# VentaConnected_Arduino_V0_01_2017-11-22.net
KiCad netlist of a schematic drawn in EAGLE
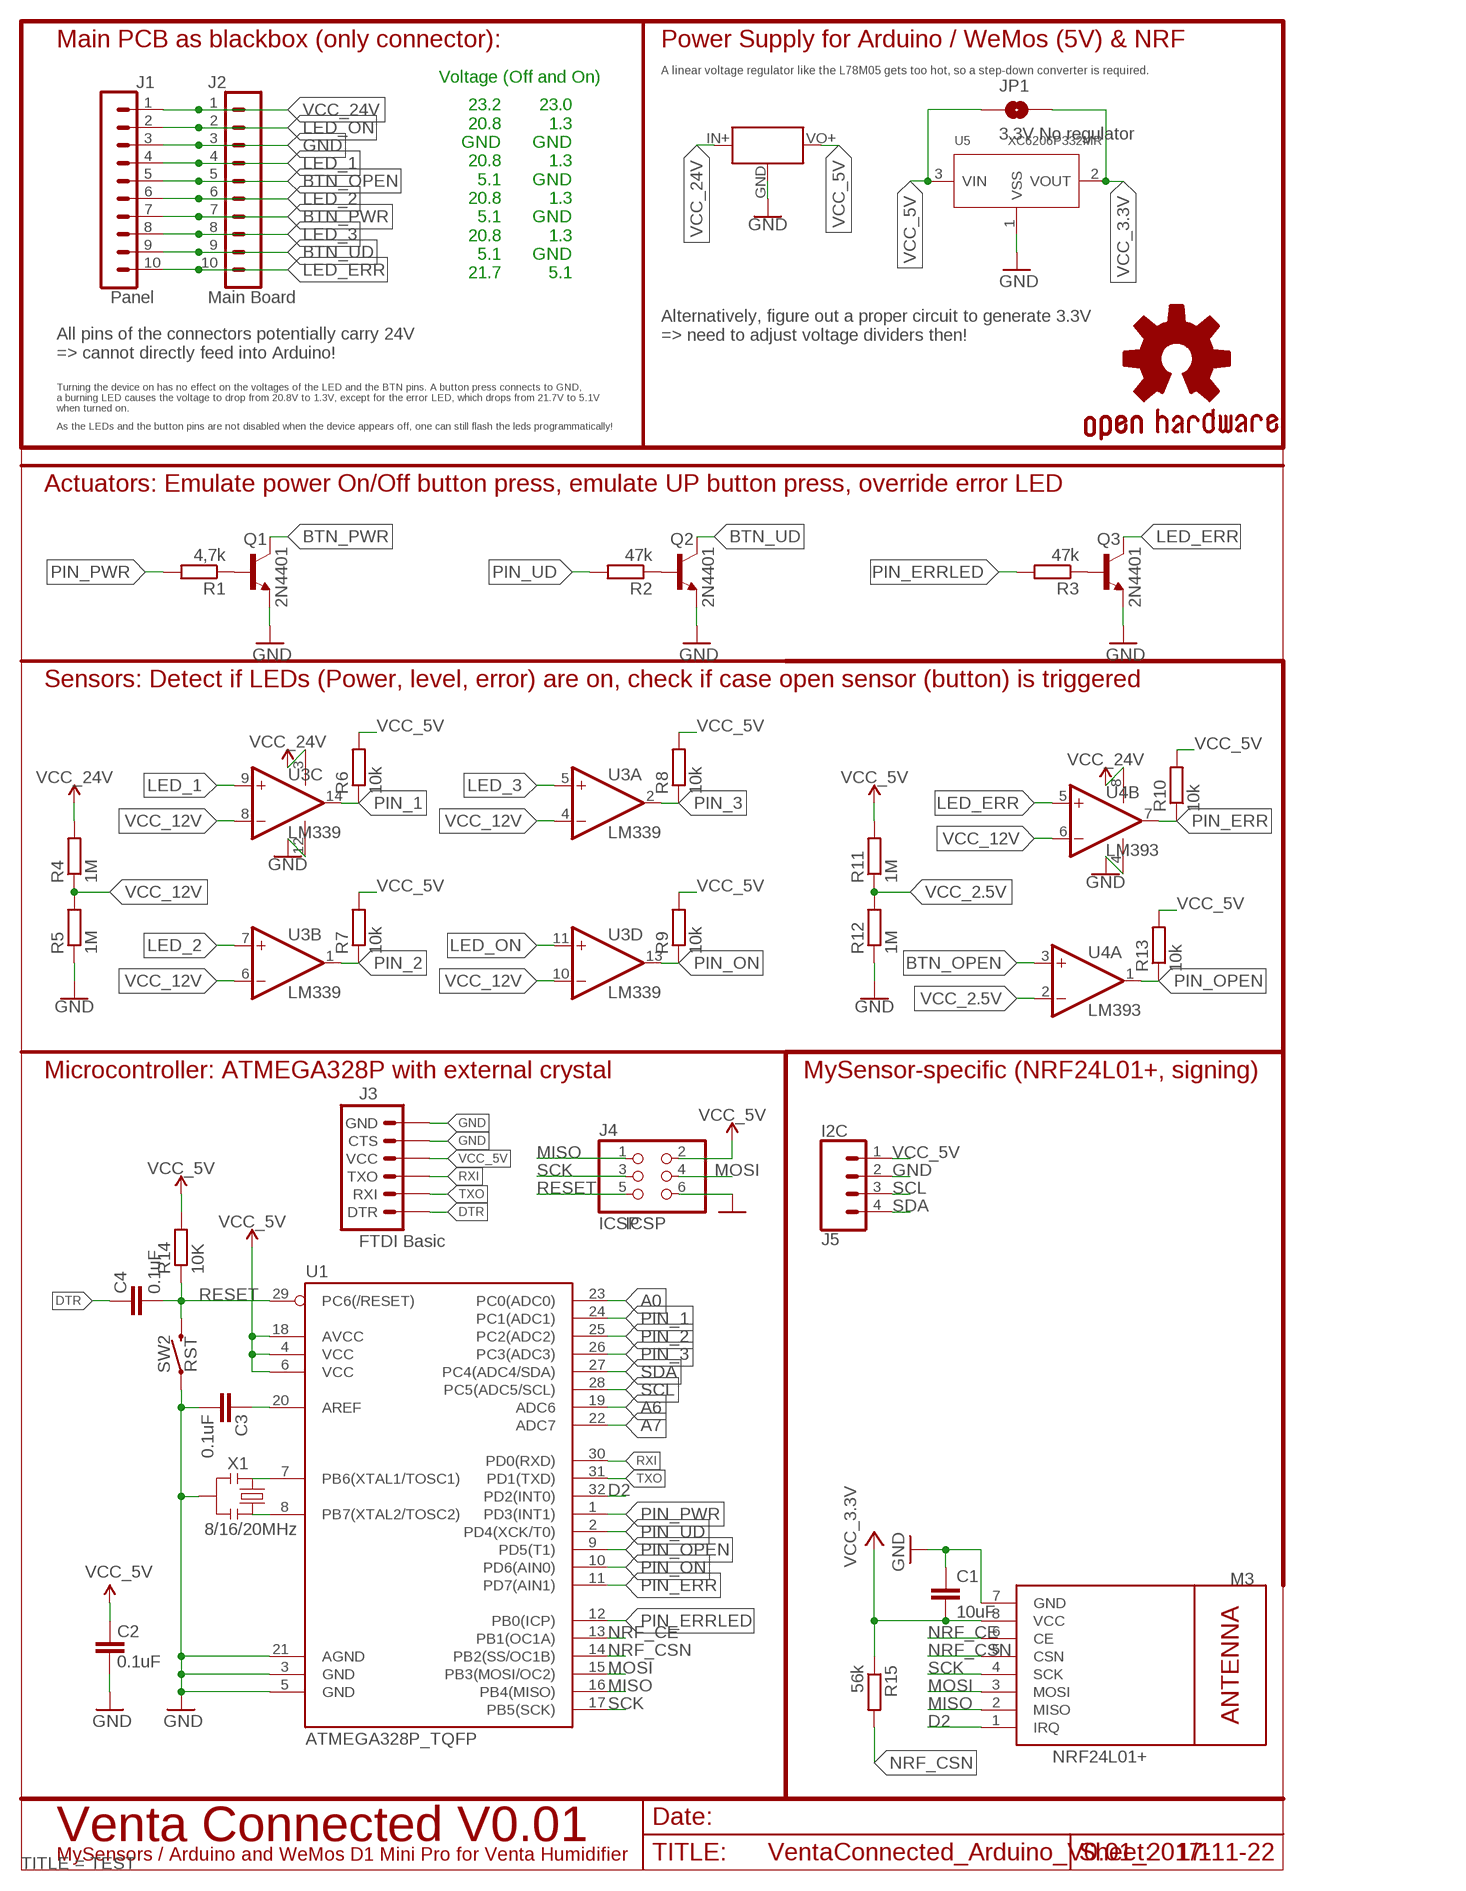
[diagram p0: schematic, sheet 1]

(export (version "E")
  (design (tool "Eeschema 10.0.6"))
  (components
    (comp (ref "C1")
      (value "10uF")
      (footprint "eagle-import:C0805")
      (libsource (lib "eagle-import") (part "C-EUC0805"))
    )
    (comp (ref "C2")
      (value "0.1uF")
      (footprint "eagle-import:0805")
      (libsource (lib "eagle-import") (part "CAP0805"))
    )
    (comp (ref "C3")
      (value "0.1uF")
      (footprint "eagle-import:0805")
      (libsource (lib "eagle-import") (part "CAP0805"))
    )
    (comp (ref "C4")
      (value "0.1uF")
      (footprint "eagle-import:0805")
      (libsource (lib "eagle-import") (part "CAP0805"))
    )
    (comp (ref "GOLD_ORB_SM1")
      (value "OSHWLOGO_GOLD_ORB_SM")
      (footprint "eagle-import:OSHW2")
      (libsource (lib "eagle-import") (part "OSHWLOGO_GOLD_ORB_SM"))
    )
    (comp (ref "J1")
      (value "Panel")
      (footprint "eagle-import:2X5-SHROUDED")
      (libsource (lib "eagle-import") (part "CONN_05X2SHD"))
    )
    (comp (ref "J2")
      (value "Main Board")
      (footprint "eagle-import:2X5")
      (libsource (lib "eagle-import") (part "CONN_05X2PTH"))
    )
    (comp (ref "J3")
      (value "FTDI Basic")
      (footprint "eagle-import:1X06")
      (libsource (lib "eagle-import") (part "ARDUINO_SERIAL_PROGRAMPTH"))
    )
    (comp (ref "J4")
      (value "ICSP")
      (footprint "eagle-import:2X03")
      (libsource (lib "eagle-import") (part "PINHD-2X3"))
    )
    (comp (ref "J5")
      (value "I2C")
      (footprint "eagle-import:1X04")
      (libsource (lib "eagle-import") (part "CONN_04"))
    )
    (comp (ref "JP1")
      (value "3.3V No regulator")
      (footprint "eagle-import:SMT-JUMPER_2_NO_SILK")
      (libsource (lib "eagle-import") (part "JUMPER-SMT_2_NO_SILK"))
    )
    (comp (ref "M3")
      (value "NRF24L01+")
      (footprint "eagle-import:WIRELESS-NRF24L01-SMD")
      (libsource (lib "eagle-import") (part "WIRELESS-NRF24L01SMD"))
    )
    (comp (ref "Q1")
      (value "2N4401")
      (footprint "eagle-import:SOT23-BEC")
      (libsource (lib "eagle-import") (part "-NPN-SOT23-BECMMBT4401LT1"))
    )
    (comp (ref "Q2")
      (value "2N4401")
      (footprint "eagle-import:SOT23-BEC")
      (libsource (lib "eagle-import") (part "-NPN-SOT23-BECMMBT4401LT1"))
    )
    (comp (ref "Q3")
      (value "2N4401")
      (footprint "eagle-import:SOT23-BEC")
      (libsource (lib "eagle-import") (part "-NPN-SOT23-BECMMBT4401LT1"))
    )
    (comp (ref "R1")
      (value "4,7k")
      (footprint "eagle-import:R0805")
      (libsource (lib "eagle-import") (part "resistor_348_R-EU_R0805"))
    )
    (comp (ref "R2")
      (value "47k")
      (footprint "eagle-import:R0805")
      (libsource (lib "eagle-import") (part "resistor_348_R-EU_R0805"))
    )
    (comp (ref "R3")
      (value "47k")
      (footprint "eagle-import:R0805")
      (libsource (lib "eagle-import") (part "resistor_348_R-EU_R0805"))
    )
    (comp (ref "R4")
      (value "1M")
      (footprint "eagle-import:R0805")
      (libsource (lib "eagle-import") (part "resistor_348_R-EU_R0805"))
    )
    (comp (ref "R5")
      (value "1M")
      (footprint "eagle-import:R0805")
      (libsource (lib "eagle-import") (part "resistor_348_R-EU_R0805"))
    )
    (comp (ref "R6")
      (value "10k")
      (footprint "eagle-import:R0805")
      (libsource (lib "eagle-import") (part "rcl_334_R-EU_R0805"))
    )
    (comp (ref "R7")
      (value "10k")
      (footprint "eagle-import:R0805")
      (libsource (lib "eagle-import") (part "rcl_334_R-EU_R0805"))
    )
    (comp (ref "R8")
      (value "10k")
      (footprint "eagle-import:R0805")
      (libsource (lib "eagle-import") (part "rcl_334_R-EU_R0805"))
    )
    (comp (ref "R9")
      (value "10k")
      (footprint "eagle-import:R0805")
      (libsource (lib "eagle-import") (part "rcl_334_R-EU_R0805"))
    )
    (comp (ref "R10")
      (value "10k")
      (footprint "eagle-import:R0805")
      (libsource (lib "eagle-import") (part "rcl_334_R-EU_R0805"))
    )
    (comp (ref "R11")
      (value "1M")
      (footprint "eagle-import:R0805")
      (libsource (lib "eagle-import") (part "resistor_348_R-EU_R0805"))
    )
    (comp (ref "R12")
      (value "1M")
      (footprint "eagle-import:R0805")
      (libsource (lib "eagle-import") (part "resistor_348_R-EU_R0805"))
    )
    (comp (ref "R13")
      (value "10k")
      (footprint "eagle-import:R0805")
      (libsource (lib "eagle-import") (part "rcl_334_R-EU_R0805"))
    )
    (comp (ref "R14")
      (value "10K")
      (footprint "eagle-import:R0805")
      (libsource (lib "eagle-import") (part "rcl_334_R-EU_R0805"))
    )
    (comp (ref "R15")
      (value "56k")
      (footprint "eagle-import:R0805")
      (libsource (lib "eagle-import") (part "R-EU_R0805"))
    )
    (comp (ref "SW2")
      (value "RST")
      (footprint "eagle-import:TACTILE_SWITCH_SMD_6.0X3.5MM")
      (libsource (lib "eagle-import") (part "MOMENTARY-SWITCH-SPST-SMD-6.0X3.5MM"))
    )
    (comp (ref "U1")
      (value "ATMEGA328P_TQFP")
      (footprint "eagle-import:TQFP32-08")
      (libsource (lib "eagle-import") (part "ATMEGA328P_TQFP"))
    )
    (comp (ref "U2")
      (value "MINI_BUCK_CONVERTER_UPSIDEDOWN")
      (footprint "eagle-import:MINI_BUCK_CONVERTER_UPDOWN")
      (libsource (lib "eagle-import") (part "MINI_BUCK_CONVERTER_UPSIDEDOWN"))
    )
    (comp (ref "U3")
      (value "LM339")
      (footprint "eagle-import:SO14")
      (libsource (lib "eagle-import") (part "TLC339D"))
    )
    (comp (ref "U4")
      (value "LM393")
      (footprint "eagle-import:SO08")
      (libsource (lib "eagle-import") (part "LM393D"))
    )
    (comp (ref "U5")
      (value "XC6206P332MR")
      (footprint "eagle-import:SOT-23")
      (fields (field (name "MPN") "XC6206P332MR-G"))
      (libsource (lib "eagle-import") (part "PMIC-LDO-XC6206P332MR-G(SOT23)"))
    )
    (comp (ref "X1")
      (value "8/16/20MHz")
      (footprint "eagle-import:RESONATOR-SMD-1_1")
      (libsource (lib "eagle-import") (part "RESONATOR1{colon}1"))
    )
  )
  (nets
    (net (code "1") (name "/D2") (class "Default")
      (node (ref "M3") (pin "1") (pinfunction "IRQ_1") (pintype "bidirectional"))
      (node (ref "U1") (pin "32") (pinfunction "PD2(INT0)_32") (pintype "bidirectional"))
    )
    (net (code "2") (name "/MISO") (class "Default")
      (node (ref "J4") (pin "1") (pinfunction "1_1") (pintype "passive"))
      (node (ref "M3") (pin "2") (pinfunction "MISO_2") (pintype "bidirectional"))
      (node (ref "U1") (pin "16") (pinfunction "PB4(MISO)_16") (pintype "bidirectional"))
    )
    (net (code "3") (name "/MOSI") (class "Default")
      (node (ref "J4") (pin "4") (pinfunction "4_4") (pintype "passive"))
      (node (ref "M3") (pin "3") (pinfunction "MOSI_3") (pintype "bidirectional"))
      (node (ref "U1") (pin "15") (pinfunction "PB3(MOSI/OC2)_15") (pintype "bidirectional"))
    )
    (net (code "4") (name "/NRF_CE") (class "Default")
      (node (ref "M3") (pin "6") (pinfunction "CE_6") (pintype "bidirectional"))
      (node (ref "U1") (pin "13") (pinfunction "PB1(OC1A)_13") (pintype "bidirectional"))
    )
    (net (code "5") (name "/RESET") (class "Default")
      (node (ref "C4") (pin "1") (pinfunction "1_1") (pintype "passive"))
      (node (ref "J4") (pin "5") (pinfunction "5_5") (pintype "passive"))
      (node (ref "R14") (pin "1") (pinfunction "1_1") (pintype "passive"))
      (node (ref "SW2") (pin "2") (pinfunction "2_2") (pintype "passive"))
      (node (ref "U1") (pin "29") (pinfunction "PC6(/RESET)_29") (pintype "bidirectional"))
    )
    (net (code "6") (name "/SCK") (class "Default")
      (node (ref "J4") (pin "3") (pinfunction "3_3") (pintype "passive"))
      (node (ref "M3") (pin "4") (pinfunction "SCK_4") (pintype "bidirectional"))
      (node (ref "U1") (pin "17") (pinfunction "PB5(SCK)_17") (pintype "bidirectional"))
    )
    (net (code "7") (name "A0") (class "Default")
      (node (ref "U1") (pin "23") (pinfunction "PC0(ADC0)_23") (pintype "bidirectional"))
    )
    (net (code "8") (name "A6") (class "Default")
      (node (ref "U1") (pin "19") (pinfunction "ADC6_19") (pintype "bidirectional"))
    )
    (net (code "9") (name "A7") (class "Default")
      (node (ref "U1") (pin "22") (pinfunction "ADC7_22") (pintype "bidirectional"))
    )
    (net (code "10") (name "BTN_OPEN") (class "Default")
      (node (ref "J1") (pin "5") (pinfunction "5_5") (pintype "passive"))
      (node (ref "J2") (pin "5") (pinfunction "5_5") (pintype "passive"))
      (node (ref "U4") (pin "3") (pinfunction "+IN_3") (pintype "input"))
    )
    (net (code "11") (name "BTN_PWR") (class "Default")
      (node (ref "J1") (pin "7") (pinfunction "7_7") (pintype "passive"))
      (node (ref "J2") (pin "7") (pinfunction "7_7") (pintype "passive"))
      (node (ref "Q1") (pin "C") (pinfunction "C_C") (pintype "passive"))
    )
    (net (code "12") (name "BTN_UD") (class "Default")
      (node (ref "J1") (pin "9") (pinfunction "9_9") (pintype "passive"))
      (node (ref "J2") (pin "9") (pinfunction "9_9") (pintype "passive"))
      (node (ref "Q2") (pin "C") (pinfunction "C_C") (pintype "passive"))
    )
    (net (code "13") (name "DTR") (class "Default")
      (node (ref "C4") (pin "2") (pinfunction "2_2") (pintype "passive"))
      (node (ref "J3") (pin "1") (pinfunction "DTR_1") (pintype "passive"))
    )
    (net (code "14") (name "GND") (class "Default")
      (node (ref "C1") (pin "1") (pinfunction "1_1") (pintype "passive"))
      (node (ref "C2") (pin "1") (pinfunction "1_1") (pintype "passive"))
      (node (ref "C3") (pin "1") (pinfunction "1_1") (pintype "passive"))
      (node (ref "J1") (pin "3") (pinfunction "3_3") (pintype "passive"))
      (node (ref "J2") (pin "3") (pinfunction "3_3") (pintype "passive"))
      (node (ref "J3") (pin "5") (pinfunction "CTS_5") (pintype "passive"))
      (node (ref "J3") (pin "6") (pinfunction "GND_6") (pintype "passive"))
      (node (ref "J4") (pin "6") (pinfunction "6_6") (pintype "passive"))
      (node (ref "J5") (pin "2") (pinfunction "2_2") (pintype "passive"))
      (node (ref "M3") (pin "7") (pinfunction "GND_7") (pintype "power_in"))
      (node (ref "Q1") (pin "E") (pinfunction "E_E") (pintype "passive"))
      (node (ref "Q2") (pin "E") (pinfunction "E_E") (pintype "passive"))
      (node (ref "Q3") (pin "E") (pinfunction "E_E") (pintype "passive"))
      (node (ref "R12") (pin "1") (pinfunction "1_1") (pintype "passive"))
      (node (ref "R5") (pin "1") (pinfunction "1_1") (pintype "passive"))
      (node (ref "SW2") (pin "1") (pinfunction "1_1") (pintype "passive"))
      (node (ref "U1") (pin "21") (pinfunction "AGND_21") (pintype "bidirectional"))
      (node (ref "U1") (pin "3") (pinfunction "GND_3") (pintype "bidirectional"))
      (node (ref "U1") (pin "5") (pinfunction "GND_5") (pintype "bidirectional"))
      (node (ref "U2") (pin "GND") (pinfunction "GND_GND") (pintype "bidirectional"))
      (node (ref "U3") (pin "12") (pinfunction "V-_12") (pintype "power_in"))
      (node (ref "U4") (pin "4") (pinfunction "V-_4") (pintype "power_in"))
      (node (ref "U5") (pin "1") (pinfunction "VSS_1") (pintype "power_in"))
      (node (ref "X1") (pin "2") (pinfunction "2_2") (pintype "passive"))
    )
    (net (code "15") (name "LED_1") (class "Default")
      (node (ref "J1") (pin "4") (pinfunction "4_4") (pintype "passive"))
      (node (ref "J2") (pin "4") (pinfunction "4_4") (pintype "passive"))
      (node (ref "U3") (pin "9") (pinfunction "+IN_9") (pintype "input"))
    )
    (net (code "16") (name "LED_2") (class "Default")
      (node (ref "J1") (pin "6") (pinfunction "6_6") (pintype "passive"))
      (node (ref "J2") (pin "6") (pinfunction "6_6") (pintype "passive"))
      (node (ref "U3") (pin "7") (pinfunction "+IN_7") (pintype "input"))
    )
    (net (code "17") (name "LED_3") (class "Default")
      (node (ref "J1") (pin "8") (pinfunction "8_8") (pintype "passive"))
      (node (ref "J2") (pin "8") (pinfunction "8_8") (pintype "passive"))
      (node (ref "U3") (pin "5") (pinfunction "+IN_5") (pintype "input"))
    )
    (net (code "18") (name "LED_ERR") (class "Default")
      (node (ref "J1") (pin "10") (pinfunction "10_10") (pintype "passive"))
      (node (ref "J2") (pin "10") (pinfunction "10_10") (pintype "passive"))
      (node (ref "Q3") (pin "C") (pinfunction "C_C") (pintype "passive"))
      (node (ref "U4") (pin "5") (pinfunction "+IN_5") (pintype "input"))
    )
    (net (code "19") (name "LED_ON") (class "Default")
      (node (ref "J1") (pin "2") (pinfunction "2_2") (pintype "passive"))
      (node (ref "J2") (pin "2") (pinfunction "2_2") (pintype "passive"))
      (node (ref "U3") (pin "11") (pinfunction "+IN_11") (pintype "input"))
    )
    (net (code "20") (name "NRF_CSN") (class "Default")
      (node (ref "M3") (pin "5") (pinfunction "CSN_5") (pintype "bidirectional"))
      (node (ref "R15") (pin "2") (pinfunction "2_2") (pintype "passive"))
      (node (ref "U1") (pin "14") (pinfunction "PB2(SS/OC1B)_14") (pintype "bidirectional"))
    )
    (net (code "21") (name "Net-(Q1-PadB)") (class "Default")
      (node (ref "Q1") (pin "B") (pinfunction "B_B") (pintype "passive"))
      (node (ref "R1") (pin "1") (pinfunction "1_1") (pintype "passive"))
    )
    (net (code "22") (name "Net-(Q2-PadB)") (class "Default")
      (node (ref "Q2") (pin "B") (pinfunction "B_B") (pintype "passive"))
      (node (ref "R2") (pin "1") (pinfunction "1_1") (pintype "passive"))
    )
    (net (code "23") (name "Net-(Q3-PadB)") (class "Default")
      (node (ref "Q3") (pin "B") (pinfunction "B_B") (pintype "passive"))
      (node (ref "R3") (pin "1") (pinfunction "1_1") (pintype "passive"))
    )
    (net (code "24") (name "Net-(U1-AREF)") (class "Default")
      (node (ref "C3") (pin "2") (pinfunction "2_2") (pintype "passive"))
      (node (ref "U1") (pin "20") (pinfunction "AREF_20") (pintype "bidirectional"))
    )
    (net (code "25") (name "Net-(U1-PB6(XTAL1{slash}TOSC1))") (class "Default")
      (node (ref "U1") (pin "7") (pinfunction "PB6(XTAL1/TOSC1)_7") (pintype "bidirectional"))
      (node (ref "X1") (pin "1") (pinfunction "1_1") (pintype "passive"))
    )
    (net (code "26") (name "Net-(U1-PB7(XTAL2{slash}TOSC2))") (class "Default")
      (node (ref "U1") (pin "8") (pinfunction "PB7(XTAL2/TOSC2)_8") (pintype "bidirectional"))
      (node (ref "X1") (pin "3") (pinfunction "3_3") (pintype "passive"))
    )
    (net (code "27") (name "PIN_1") (class "Default")
      (node (ref "R6") (pin "1") (pinfunction "1_1") (pintype "passive"))
      (node (ref "U1") (pin "24") (pinfunction "PC1(ADC1)_24") (pintype "bidirectional"))
      (node (ref "U3") (pin "14") (pinfunction "OUT_14") (pintype "output"))
    )
    (net (code "28") (name "PIN_2") (class "Default")
      (node (ref "R7") (pin "1") (pinfunction "1_1") (pintype "passive"))
      (node (ref "U1") (pin "25") (pinfunction "PC2(ADC2)_25") (pintype "bidirectional"))
      (node (ref "U3") (pin "1") (pinfunction "OUT_1") (pintype "output"))
    )
    (net (code "29") (name "PIN_3") (class "Default")
      (node (ref "R8") (pin "1") (pinfunction "1_1") (pintype "passive"))
      (node (ref "U1") (pin "26") (pinfunction "PC3(ADC3)_26") (pintype "bidirectional"))
      (node (ref "U3") (pin "2") (pinfunction "OUT_2") (pintype "output"))
    )
    (net (code "30") (name "PIN_ERR") (class "Default")
      (node (ref "R10") (pin "1") (pinfunction "1_1") (pintype "passive"))
      (node (ref "U1") (pin "11") (pinfunction "PD7(AIN1)_11") (pintype "bidirectional"))
      (node (ref "U4") (pin "7") (pinfunction "OUT_7") (pintype "output"))
    )
    (net (code "31") (name "PIN_ERRLED") (class "Default")
      (node (ref "R3") (pin "2") (pinfunction "2_2") (pintype "passive"))
      (node (ref "U1") (pin "12") (pinfunction "PB0(ICP)_12") (pintype "bidirectional"))
    )
    (net (code "32") (name "PIN_ON") (class "Default")
      (node (ref "R9") (pin "1") (pinfunction "1_1") (pintype "passive"))
      (node (ref "U1") (pin "10") (pinfunction "PD6(AIN0)_10") (pintype "bidirectional"))
      (node (ref "U3") (pin "13") (pinfunction "OUT_13") (pintype "output"))
    )
    (net (code "33") (name "PIN_OPEN") (class "Default")
      (node (ref "R13") (pin "1") (pinfunction "1_1") (pintype "passive"))
      (node (ref "U1") (pin "9") (pinfunction "PD5(T1)_9") (pintype "bidirectional"))
      (node (ref "U4") (pin "1") (pinfunction "OUT_1") (pintype "output"))
    )
    (net (code "34") (name "PIN_PWR") (class "Default")
      (node (ref "R1") (pin "2") (pinfunction "2_2") (pintype "passive"))
      (node (ref "U1") (pin "1") (pinfunction "PD3(INT1)_1") (pintype "bidirectional"))
    )
    (net (code "35") (name "PIN_UD") (class "Default")
      (node (ref "R2") (pin "2") (pinfunction "2_2") (pintype "passive"))
      (node (ref "U1") (pin "2") (pinfunction "PD4(XCK/T0)_2") (pintype "bidirectional"))
    )
    (net (code "36") (name "RXI") (class "Default")
      (node (ref "J3") (pin "3") (pinfunction "TXO_3") (pintype "passive"))
      (node (ref "U1") (pin "30") (pinfunction "PD0(RXD)_30") (pintype "bidirectional"))
    )
    (net (code "37") (name "SCL") (class "Default")
      (node (ref "J5") (pin "3") (pinfunction "3_3") (pintype "passive"))
      (node (ref "U1") (pin "28") (pinfunction "PC5(ADC5/SCL)_28") (pintype "bidirectional"))
    )
    (net (code "38") (name "SDA") (class "Default")
      (node (ref "J5") (pin "4") (pinfunction "4_4") (pintype "passive"))
      (node (ref "U1") (pin "27") (pinfunction "PC4(ADC4/SDA)_27") (pintype "bidirectional"))
    )
    (net (code "39") (name "TXO") (class "Default")
      (node (ref "J3") (pin "2") (pinfunction "RXI_2") (pintype "passive"))
      (node (ref "U1") (pin "31") (pinfunction "PD1(TXD)_31") (pintype "bidirectional"))
    )
    (net (code "40") (name "VCC_2.5V") (class "Default")
      (node (ref "R11") (pin "1") (pinfunction "1_1") (pintype "passive"))
      (node (ref "R12") (pin "2") (pinfunction "2_2") (pintype "passive"))
      (node (ref "U4") (pin "2") (pinfunction "-IN_2") (pintype "input"))
    )
    (net (code "41") (name "VCC_3.3V") (class "Default")
      (node (ref "C1") (pin "2") (pinfunction "2_2") (pintype "passive"))
      (node (ref "JP1") (pin "2") (pinfunction "2_2") (pintype "passive"))
      (node (ref "M3") (pin "8") (pinfunction "VCC_8") (pintype "power_in"))
      (node (ref "R15") (pin "1") (pinfunction "1_1") (pintype "passive"))
      (node (ref "U5") (pin "2") (pinfunction "VOUT_2") (pintype "output"))
    )
    (net (code "42") (name "VCC_5V") (class "Default")
      (node (ref "C2") (pin "2") (pinfunction "2_2") (pintype "passive"))
      (node (ref "J3") (pin "4") (pinfunction "VCC_4") (pintype "passive"))
      (node (ref "J4") (pin "2") (pinfunction "2_2") (pintype "passive"))
      (node (ref "J5") (pin "1") (pinfunction "1_1") (pintype "passive"))
      (node (ref "JP1") (pin "1") (pinfunction "1_1") (pintype "passive"))
      (node (ref "R10") (pin "2") (pinfunction "2_2") (pintype "passive"))
      (node (ref "R11") (pin "2") (pinfunction "2_2") (pintype "passive"))
      (node (ref "R13") (pin "2") (pinfunction "2_2") (pintype "passive"))
      (node (ref "R14") (pin "2") (pinfunction "2_2") (pintype "passive"))
      (node (ref "R6") (pin "2") (pinfunction "2_2") (pintype "passive"))
      (node (ref "R7") (pin "2") (pinfunction "2_2") (pintype "passive"))
      (node (ref "R8") (pin "2") (pinfunction "2_2") (pintype "passive"))
      (node (ref "R9") (pin "2") (pinfunction "2_2") (pintype "passive"))
      (node (ref "U1") (pin "18") (pinfunction "AVCC_18") (pintype "bidirectional"))
      (node (ref "U1") (pin "4") (pinfunction "VCC_4") (pintype "bidirectional"))
      (node (ref "U1") (pin "6") (pinfunction "VCC_6") (pintype "bidirectional"))
      (node (ref "U2") (pin "VO+") (pinfunction "VOUT_VO+") (pintype "power_in"))
      (node (ref "U5") (pin "3") (pinfunction "VIN_3") (pintype "input"))
    )
    (net (code "43") (name "VCC_12V") (class "Default")
      (node (ref "R4") (pin "1") (pinfunction "1_1") (pintype "passive"))
      (node (ref "R5") (pin "2") (pinfunction "2_2") (pintype "passive"))
      (node (ref "U3") (pin "10") (pinfunction "-IN_10") (pintype "input"))
      (node (ref "U3") (pin "4") (pinfunction "-IN_4") (pintype "input"))
      (node (ref "U3") (pin "6") (pinfunction "-IN_6") (pintype "input"))
      (node (ref "U3") (pin "8") (pinfunction "-IN_8") (pintype "input"))
      (node (ref "U4") (pin "6") (pinfunction "-IN_6") (pintype "input"))
    )
    (net (code "44") (name "VCC_24V") (class "Default")
      (node (ref "J1") (pin "1") (pinfunction "1_1") (pintype "passive"))
      (node (ref "J2") (pin "1") (pinfunction "1_1") (pintype "passive"))
      (node (ref "R4") (pin "2") (pinfunction "2_2") (pintype "passive"))
      (node (ref "U2") (pin "IN+") (pinfunction "VIN_IN+") (pintype "input"))
      (node (ref "U3") (pin "3") (pinfunction "V+_3") (pintype "power_in"))
      (node (ref "U4") (pin "8") (pinfunction "V+_8") (pintype "power_in"))
    )
  )
)
